# Projek.net
KiCad netlist of a schematic drawn in EAGLE
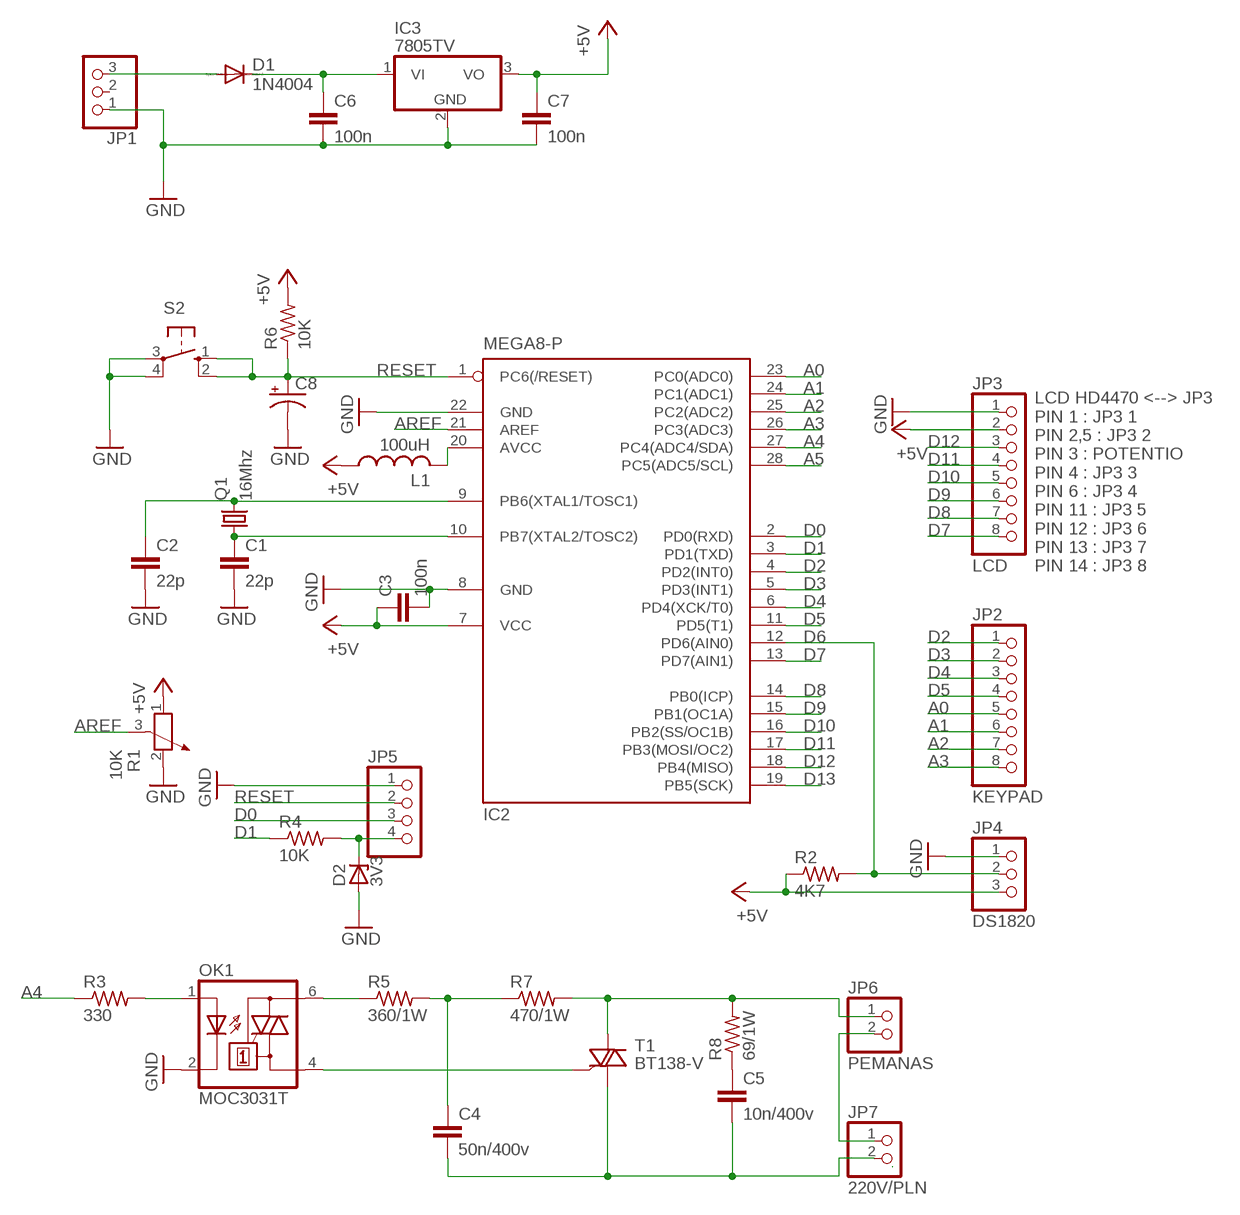
[diagram p0: schematic, sheet 1]

(export (version "E")
  (design (tool "Eeschema 10.0.6"))
  (components
    (comp (ref "C1")
      (value "22p")
      (footprint "eagle-import:C025-025X050")
      (libsource (lib "eagle-import") (part "C-EU025-025X050"))
    )
    (comp (ref "C2")
      (value "22p")
      (footprint "eagle-import:C025-025X050")
      (libsource (lib "eagle-import") (part "C-EU025-025X050"))
    )
    (comp (ref "C3")
      (value "100n")
      (footprint "eagle-import:C050-025X075")
      (libsource (lib "eagle-import") (part "C-EU050-025X075"))
    )
    (comp (ref "C4")
      (value "50n/400v")
      (footprint "eagle-import:C150-064X183")
      (libsource (lib "eagle-import") (part "C-EU150-064X183"))
    )
    (comp (ref "C5")
      (value "10n/400v")
      (footprint "eagle-import:C150-064X183")
      (libsource (lib "eagle-import") (part "C-EU150-064X183"))
    )
    (comp (ref "C6")
      (value "100n")
      (footprint "eagle-import:C050-025X075")
      (libsource (lib "eagle-import") (part "C-EU050-025X075"))
    )
    (comp (ref "C7")
      (value "100n")
      (footprint "eagle-import:C050-025X075")
      (libsource (lib "eagle-import") (part "C-EU050-025X075"))
    )
    (comp (ref "C8")
      (value "CPOL-USE2-5")
      (footprint "eagle-import:E2-5")
      (libsource (lib "eagle-import") (part "CPOL-USE2-5"))
    )
    (comp (ref "D1")
      (value "1N4004")
      (footprint "eagle-import:DO41-10")
      (libsource (lib "eagle-import") (part "1N4004"))
    )
    (comp (ref "D2")
      (value "3V3")
      (footprint "eagle-import:DO35Z10")
      (libsource (lib "eagle-import") (part "ZENER-DIODEDO35Z10"))
    )
    (comp (ref "IC2")
      (value "MEGA8-P")
      (footprint "eagle-import:DIL28-3")
      (libsource (lib "eagle-import") (part "MEGA8-P"))
    )
    (comp (ref "IC3")
      (value "7805TV")
      (footprint "eagle-import:TO220V")
      (libsource (lib "eagle-import") (part "78TV05"))
    )
    (comp (ref "JP1")
      (value "PINHD-1X3")
      (footprint "eagle-import:1X03")
      (libsource (lib "eagle-import") (part "PINHD-1X3"))
    )
    (comp (ref "JP2")
      (value "KEYPAD")
      (footprint "eagle-import:1X08")
      (libsource (lib "eagle-import") (part "PINHD-1X8"))
    )
    (comp (ref "JP3")
      (value "LCD")
      (footprint "eagle-import:1X08")
      (libsource (lib "eagle-import") (part "PINHD-1X8"))
    )
    (comp (ref "JP4")
      (value "DS1820")
      (footprint "eagle-import:1X03")
      (libsource (lib "eagle-import") (part "PINHD-1X3"))
    )
    (comp (ref "JP5")
      (value "PINHD-1X4")
      (footprint "eagle-import:1X04")
      (libsource (lib "eagle-import") (part "PINHD-1X4"))
    )
    (comp (ref "JP6")
      (value "PEMANAS")
      (footprint "eagle-import:1X02")
      (libsource (lib "eagle-import") (part "PINHD-1X2"))
    )
    (comp (ref "JP7")
      (value "220V/PLN")
      (footprint "eagle-import:1X02")
      (libsource (lib "eagle-import") (part "PINHD-1X2"))
    )
    (comp (ref "L1")
      (value "100uH")
      (footprint "eagle-import:0207_10")
      (libsource (lib "eagle-import") (part "L-US0207/10"))
    )
    (comp (ref "OK1")
      (value "MOC3031T")
      (footprint "eagle-import:DIL06B")
      (libsource (lib "eagle-import") (part "MOC30T31"))
    )
    (comp (ref "Q1")
      (value "16Mhz")
      (footprint "eagle-import:HC49U70")
      (libsource (lib "eagle-import") (part "CRYSTALHC49U70"))
    )
    (comp (ref "R1")
      (value "10K")
      (footprint "eagle-import:PT-10")
      (libsource (lib "eagle-import") (part "POTENTIOMETER_PT-10"))
    )
    (comp (ref "R2")
      (value "4K7")
      (footprint "eagle-import:0309_10")
      (libsource (lib "eagle-import") (part "R-US_0309/10"))
    )
    (comp (ref "R3")
      (value "330")
      (footprint "eagle-import:0309_10")
      (libsource (lib "eagle-import") (part "R-US_0309/10"))
    )
    (comp (ref "R4")
      (value "10K")
      (footprint "eagle-import:0309_10")
      (libsource (lib "eagle-import") (part "R-US_0309/10"))
    )
    (comp (ref "R5")
      (value "360/1W")
      (footprint "eagle-import:0414_15")
      (libsource (lib "eagle-import") (part "R-US_0414/15"))
    )
    (comp (ref "R6")
      (value "10K")
      (footprint "eagle-import:0309_10")
      (libsource (lib "eagle-import") (part "R-US_0309/10"))
    )
    (comp (ref "R7")
      (value "470/1W")
      (footprint "eagle-import:0414_15")
      (libsource (lib "eagle-import") (part "R-US_0414/15"))
    )
    (comp (ref "R8")
      (value "69/1W")
      (footprint "eagle-import:0414_15")
      (libsource (lib "eagle-import") (part "R-US_0414/15"))
    )
    (comp (ref "S2")
      (value "10-XX")
      (footprint "eagle-import:B3F-10XX")
      (fields (field (name "MPN") "B3F-1000"))
      (libsource (lib "eagle-import") (part "10-XX"))
    )
    (comp (ref "T1")
      (value "BT138-V")
      (footprint "eagle-import:TO220BV")
      (libsource (lib "eagle-import") (part "BT138-V"))
    )
  )
  (nets
    (net (code "1") (name "+5V") (class "Default")
      (node (ref "C3") (pin "1") (pinfunction "1_1") (pintype "passive"))
      (node (ref "C7") (pin "1") (pinfunction "1_1") (pintype "passive"))
      (node (ref "IC2") (pin "7") (pinfunction "VCC_7") (pintype "power_in"))
      (node (ref "IC3") (pin "3") (pinfunction "VO_3") (pintype "passive"))
      (node (ref "JP3") (pin "2") (pinfunction "2_2") (pintype "passive"))
      (node (ref "JP4") (pin "3") (pinfunction "3_3") (pintype "passive"))
      (node (ref "L1") (pin "1") (pinfunction "1_1") (pintype "passive"))
      (node (ref "R1") (pin "1") (pinfunction "1_1") (pintype "passive"))
      (node (ref "R2") (pin "1") (pinfunction "1_1") (pintype "passive"))
      (node (ref "R6") (pin "2") (pinfunction "2_2") (pintype "passive"))
    )
    (net (code "2") (name "/A0") (class "Default")
      (node (ref "IC2") (pin "23") (pinfunction "PC0(ADC0)_23") (pintype "bidirectional"))
      (node (ref "JP2") (pin "5") (pinfunction "5_5") (pintype "passive"))
    )
    (net (code "3") (name "/A1") (class "Default")
      (node (ref "IC2") (pin "24") (pinfunction "PC1(ADC1)_24") (pintype "bidirectional"))
      (node (ref "JP2") (pin "6") (pinfunction "6_6") (pintype "passive"))
    )
    (net (code "4") (name "/A2") (class "Default")
      (node (ref "IC2") (pin "25") (pinfunction "PC2(ADC2)_25") (pintype "bidirectional"))
      (node (ref "JP2") (pin "7") (pinfunction "7_7") (pintype "passive"))
    )
    (net (code "5") (name "/A3") (class "Default")
      (node (ref "IC2") (pin "26") (pinfunction "PC3(ADC3)_26") (pintype "bidirectional"))
      (node (ref "JP2") (pin "8") (pinfunction "8_8") (pintype "passive"))
    )
    (net (code "6") (name "/A4") (class "Default")
      (node (ref "IC2") (pin "27") (pinfunction "PC4(ADC4/SDA)_27") (pintype "bidirectional"))
      (node (ref "R3") (pin "1") (pinfunction "1_1") (pintype "passive"))
    )
    (net (code "7") (name "/A5") (class "Default")
      (node (ref "IC2") (pin "28") (pinfunction "PC5(ADC5/SCL)_28") (pintype "bidirectional"))
    )
    (net (code "8") (name "/AREF") (class "Default")
      (node (ref "IC2") (pin "21") (pinfunction "AREF_21") (pintype "passive"))
      (node (ref "R1") (pin "3") (pinfunction "3_3") (pintype "passive"))
    )
    (net (code "9") (name "/D0") (class "Default")
      (node (ref "IC2") (pin "2") (pinfunction "PD0(RXD)_2") (pintype "bidirectional"))
      (node (ref "JP5") (pin "3") (pinfunction "3_3") (pintype "passive"))
    )
    (net (code "10") (name "/D1") (class "Default")
      (node (ref "IC2") (pin "3") (pinfunction "PD1(TXD)_3") (pintype "bidirectional"))
      (node (ref "R4") (pin "1") (pinfunction "1_1") (pintype "passive"))
    )
    (net (code "11") (name "/D2") (class "Default")
      (node (ref "IC2") (pin "4") (pinfunction "PD2(INT0)_4") (pintype "bidirectional"))
      (node (ref "JP2") (pin "1") (pinfunction "1_1") (pintype "passive"))
    )
    (net (code "12") (name "/D3") (class "Default")
      (node (ref "IC2") (pin "5") (pinfunction "PD3(INT1)_5") (pintype "bidirectional"))
      (node (ref "JP2") (pin "2") (pinfunction "2_2") (pintype "passive"))
    )
    (net (code "13") (name "/D4") (class "Default")
      (node (ref "IC2") (pin "6") (pinfunction "PD4(XCK/T0)_6") (pintype "bidirectional"))
      (node (ref "JP2") (pin "3") (pinfunction "3_3") (pintype "passive"))
    )
    (net (code "14") (name "/D5") (class "Default")
      (node (ref "IC2") (pin "11") (pinfunction "PD5(T1)_11") (pintype "bidirectional"))
      (node (ref "JP2") (pin "4") (pinfunction "4_4") (pintype "passive"))
    )
    (net (code "15") (name "/D6") (class "Default")
      (node (ref "IC2") (pin "12") (pinfunction "PD6(AIN0)_12") (pintype "bidirectional"))
      (node (ref "JP4") (pin "2") (pinfunction "2_2") (pintype "passive"))
      (node (ref "R2") (pin "2") (pinfunction "2_2") (pintype "passive"))
    )
    (net (code "16") (name "/D7") (class "Default")
      (node (ref "IC2") (pin "13") (pinfunction "PD7(AIN1)_13") (pintype "bidirectional"))
      (node (ref "JP3") (pin "8") (pinfunction "8_8") (pintype "passive"))
    )
    (net (code "17") (name "/D8") (class "Default")
      (node (ref "IC2") (pin "14") (pinfunction "PB0(ICP)_14") (pintype "bidirectional"))
      (node (ref "JP3") (pin "7") (pinfunction "7_7") (pintype "passive"))
    )
    (net (code "18") (name "/D9") (class "Default")
      (node (ref "IC2") (pin "15") (pinfunction "PB1(OC1A)_15") (pintype "bidirectional"))
      (node (ref "JP3") (pin "6") (pinfunction "6_6") (pintype "passive"))
    )
    (net (code "19") (name "/D10") (class "Default")
      (node (ref "IC2") (pin "16") (pinfunction "PB2(SS/OC1B)_16") (pintype "bidirectional"))
      (node (ref "JP3") (pin "5") (pinfunction "5_5") (pintype "passive"))
    )
    (net (code "20") (name "/D11") (class "Default")
      (node (ref "IC2") (pin "17") (pinfunction "PB3(MOSI/OC2)_17") (pintype "bidirectional"))
      (node (ref "JP3") (pin "4") (pinfunction "4_4") (pintype "passive"))
    )
    (net (code "21") (name "/D12") (class "Default")
      (node (ref "IC2") (pin "18") (pinfunction "PB4(MISO)_18") (pintype "bidirectional"))
      (node (ref "JP3") (pin "3") (pinfunction "3_3") (pintype "passive"))
    )
    (net (code "22") (name "/D13") (class "Default")
      (node (ref "IC2") (pin "19") (pinfunction "PB5(SCK)_19") (pintype "bidirectional"))
    )
    (net (code "23") (name "/RESET") (class "Default")
      (node (ref "C8") (pin "+") (pinfunction "+_+") (pintype "passive"))
      (node (ref "IC2") (pin "1") (pinfunction "PC6(/RESET)_1") (pintype "bidirectional"))
      (node (ref "JP5") (pin "2") (pinfunction "2_2") (pintype "passive"))
      (node (ref "R6") (pin "1") (pinfunction "1_1") (pintype "passive"))
      (node (ref "S2") (pin "1") (pinfunction "S_1") (pintype "passive"))
      (node (ref "S2") (pin "2") (pinfunction "S1_2") (pintype "passive"))
    )
    (net (code "24") (name "GND") (class "Default")
      (node (ref "C1") (pin "2") (pinfunction "2_2") (pintype "passive"))
      (node (ref "C2") (pin "2") (pinfunction "2_2") (pintype "passive"))
      (node (ref "C3") (pin "2") (pinfunction "2_2") (pintype "passive"))
      (node (ref "C6") (pin "2") (pinfunction "2_2") (pintype "passive"))
      (node (ref "C7") (pin "2") (pinfunction "2_2") (pintype "passive"))
      (node (ref "C8") (pin "-") (pinfunction "-_-") (pintype "passive"))
      (node (ref "D2") (pin "A") (pinfunction "A_A") (pintype "passive"))
      (node (ref "IC2") (pin "22") (pinfunction "GND_22") (pintype "power_in"))
      (node (ref "IC2") (pin "8") (pinfunction "GND_8") (pintype "power_in"))
      (node (ref "IC3") (pin "2") (pinfunction "GND_2") (pintype "passive"))
      (node (ref "JP1") (pin "1") (pinfunction "1_1") (pintype "passive"))
      (node (ref "JP3") (pin "1") (pinfunction "1_1") (pintype "passive"))
      (node (ref "JP4") (pin "1") (pinfunction "1_1") (pintype "passive"))
      (node (ref "JP5") (pin "1") (pinfunction "1_1") (pintype "passive"))
      (node (ref "OK1") (pin "2") (pinfunction "C_2") (pintype "passive"))
      (node (ref "R1") (pin "2") (pinfunction "2_2") (pintype "passive"))
      (node (ref "S2") (pin "3") (pinfunction "P_3") (pintype "passive"))
      (node (ref "S2") (pin "4") (pinfunction "P1_4") (pintype "passive"))
    )
    (net (code "25") (name "Net-(C4-Pad1)") (class "Default")
      (node (ref "C4") (pin "1") (pinfunction "1_1") (pintype "passive"))
      (node (ref "R5") (pin "2") (pinfunction "2_2") (pintype "passive"))
      (node (ref "R7") (pin "1") (pinfunction "1_1") (pintype "passive"))
    )
    (net (code "26") (name "Net-(C5-Pad1)") (class "Default")
      (node (ref "C5") (pin "1") (pinfunction "1_1") (pintype "passive"))
      (node (ref "R8") (pin "1") (pinfunction "1_1") (pintype "passive"))
    )
    (net (code "27") (name "Net-(D1-PadA)") (class "Default")
      (node (ref "D1") (pin "A") (pinfunction "A_A") (pintype "passive"))
      (node (ref "JP1") (pin "3") (pinfunction "3_3") (pintype "passive"))
    )
    (net (code "28") (name "Net-(D2-PadC)") (class "Default")
      (node (ref "D2") (pin "C") (pinfunction "C_C") (pintype "passive"))
      (node (ref "JP5") (pin "4") (pinfunction "4_4") (pintype "passive"))
      (node (ref "R4") (pin "2") (pinfunction "2_2") (pintype "passive"))
    )
    (net (code "29") (name "Net-(IC2-AVCC)") (class "Default")
      (node (ref "IC2") (pin "20") (pinfunction "AVCC_20") (pintype "power_in"))
      (node (ref "L1") (pin "2") (pinfunction "2_2") (pintype "passive"))
    )
    (net (code "30") (name "Net-(IC2-PB6(XTAL1{slash}TOSC1))") (class "Default")
      (node (ref "C2") (pin "1") (pinfunction "1_1") (pintype "passive"))
      (node (ref "IC2") (pin "9") (pinfunction "PB6(XTAL1/TOSC1)_9") (pintype "bidirectional"))
      (node (ref "Q1") (pin "2") (pinfunction "2_2") (pintype "passive"))
    )
    (net (code "31") (name "Net-(IC2-PB7(XTAL2{slash}TOSC2))") (class "Default")
      (node (ref "C1") (pin "1") (pinfunction "1_1") (pintype "passive"))
      (node (ref "IC2") (pin "10") (pinfunction "PB7(XTAL2/TOSC2)_10") (pintype "bidirectional"))
      (node (ref "Q1") (pin "1") (pinfunction "1_1") (pintype "passive"))
    )
    (net (code "32") (name "Net-(IC3-VI)") (class "Default")
      (node (ref "C6") (pin "1") (pinfunction "1_1") (pintype "passive"))
      (node (ref "D1") (pin "C") (pinfunction "C_C") (pintype "passive"))
      (node (ref "IC3") (pin "1") (pinfunction "VI_1") (pintype "input"))
    )
    (net (code "33") (name "Net-(JP6-Pad2)") (class "Default")
      (node (ref "JP6") (pin "2") (pinfunction "2_2") (pintype "passive"))
      (node (ref "JP7") (pin "1") (pinfunction "1_1") (pintype "passive"))
    )
    (net (code "34") (name "Net-(OK1-A)") (class "Default")
      (node (ref "OK1") (pin "1") (pinfunction "A_1") (pintype "passive"))
      (node (ref "R3") (pin "2") (pinfunction "2_2") (pintype "passive"))
    )
    (net (code "35") (name "Net-(OK1-A1)") (class "Default")
      (node (ref "OK1") (pin "4") (pinfunction "A1_4") (pintype "passive"))
      (node (ref "T1") (pin "G") (pinfunction "G_G") (pintype "passive"))
    )
    (net (code "36") (name "Net-(OK1-A2)") (class "Default")
      (node (ref "OK1") (pin "6") (pinfunction "A2_6") (pintype "passive"))
      (node (ref "R5") (pin "1") (pinfunction "1_1") (pintype "passive"))
    )
    (net (code "37") (name "Net-(T1-A1)") (class "Default")
      (node (ref "C4") (pin "2") (pinfunction "2_2") (pintype "passive"))
      (node (ref "C5") (pin "2") (pinfunction "2_2") (pintype "passive"))
      (node (ref "JP7") (pin "2") (pinfunction "2_2") (pintype "passive"))
      (node (ref "T1") (pin "T1") (pinfunction "A1_T1") (pintype "passive"))
    )
    (net (code "38") (name "Net-(T1-A2)") (class "Default")
      (node (ref "JP6") (pin "1") (pinfunction "1_1") (pintype "passive"))
      (node (ref "R7") (pin "2") (pinfunction "2_2") (pintype "passive"))
      (node (ref "R8") (pin "2") (pinfunction "2_2") (pintype "passive"))
      (node (ref "T1") (pin "T2") (pinfunction "A2_T2") (pintype "passive"))
    )
    (net (code "39") (name "unconnected-(JP1-Pad2)") (class "Default")
      (node (ref "JP1") (pin "2") (pinfunction "2_2") (pintype "passive"))
    )
  )
)
